# Rotary_Encoder.net
KiCad netlist of a schematic drawn in Altium Designer
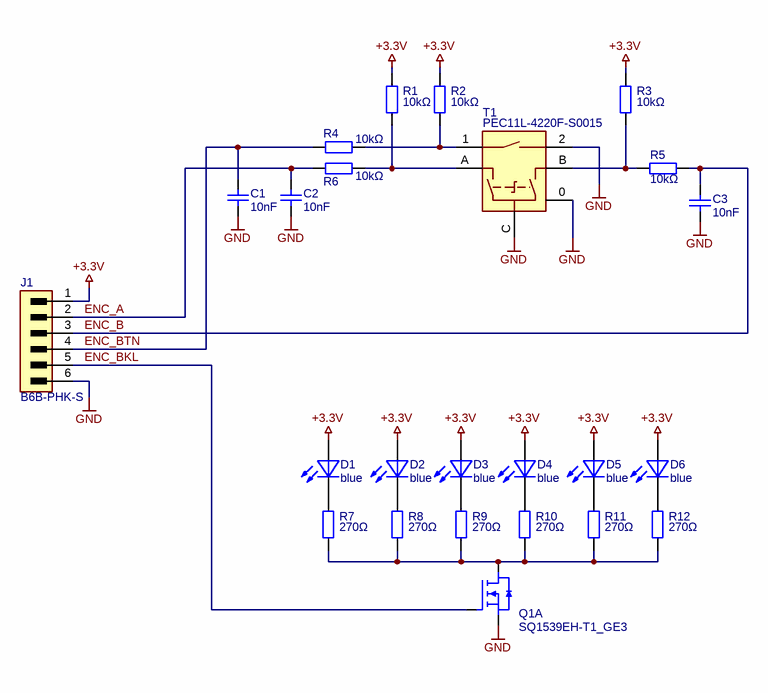
[diagram p0: Rotary Encoder.SchDoc]

(export (version "E")
  (design (tool "Eeschema 10.0.6"))
  (components
    (comp (ref "C1")
      (value "10nF")
      (footprint "SMD0603CAP")
      (description "Ceramic Capacitor")
      (libsource (lib "Audio-Streamer") (part "Capacitor Ceramic"))
    )
    (comp (ref "C2")
      (value "10nF")
      (footprint "SMD0603CAP")
      (description "Ceramic Capacitor")
      (libsource (lib "Audio-Streamer") (part "Capacitor Ceramic"))
    )
    (comp (ref "C3")
      (value "10nF")
      (footprint "SMD0603CAP")
      (description "Ceramic Capacitor")
      (libsource (lib "Audio-Streamer") (part "Capacitor Ceramic"))
    )
    (comp (ref "D1")
      (value "blue")
      (footprint "LED")
      (description "LED red")
      (fields (field (name "MANUFACTURER PART NO.") "LB M673-M1N2-35-Z"))
      (libsource (lib "Audio-Streamer") (part "LED red"))
    )
    (comp (ref "D2")
      (value "blue")
      (footprint "LED")
      (description "LED red")
      (fields (field (name "MANUFACTURER PART NO.") "LB M673-M1N2-35-Z"))
      (libsource (lib "Audio-Streamer") (part "LED red"))
    )
    (comp (ref "D3")
      (value "blue")
      (footprint "LED")
      (description "LED red")
      (fields (field (name "MANUFACTURER PART NO.") "LB M673-M1N2-35-Z"))
      (libsource (lib "Audio-Streamer") (part "LED red"))
    )
    (comp (ref "D4")
      (value "blue")
      (footprint "LED")
      (description "LED red")
      (fields (field (name "MANUFACTURER PART NO.") "LB M673-M1N2-35-Z"))
      (libsource (lib "Audio-Streamer") (part "LED red"))
    )
    (comp (ref "D5")
      (value "blue")
      (footprint "LED")
      (description "LED red")
      (fields (field (name "MANUFACTURER PART NO.") "LB M673-M1N2-35-Z"))
      (libsource (lib "Audio-Streamer") (part "LED red"))
    )
    (comp (ref "D6")
      (value "blue")
      (footprint "LED")
      (description "LED red")
      (fields (field (name "MANUFACTURER PART NO.") "LB M673-M1N2-35-Z"))
      (libsource (lib "Audio-Streamer") (part "LED red"))
    )
    (comp (ref "J1")
      (value "B6B-PHK-S")
      (footprint "B6B-PH-K-S")
      (description "Connector 6x1P")
      (libsource (lib "Audio-Streamer") (part "Connector 6x1P"))
    )
    (comp (ref "Q1")
      (value "SQ1539EH-T1_GE3")
      (footprint "SOT-363-6")
      (description "Transistor Dual, NMOS & PMOS")
      (libsource (lib "Audio-Streamer") (part "Transistor N/PMOS Dual"))
    )
    (comp (ref "R1")
      (value "10kΩ")
      (footprint "SMD0603RES")
      (description "Resistor")
      (libsource (lib "") (part "Resistor_1"))
    )
    (comp (ref "R2")
      (value "10kΩ")
      (footprint "SMD0603RES")
      (description "Resistor")
      (libsource (lib "") (part "Resistor_1"))
    )
    (comp (ref "R3")
      (value "10kΩ")
      (footprint "SMD0603RES")
      (description "Resistor")
      (libsource (lib "") (part "Resistor_2"))
    )
    (comp (ref "R4")
      (value "10kΩ")
      (footprint "SMD0603RES")
      (description "Resistor")
      (libsource (lib "Audio-Streamer") (part "Resistor"))
    )
    (comp (ref "R5")
      (value "10kΩ")
      (footprint "SMD0603RES")
      (description "Resistor")
      (libsource (lib "") (part "Resistor_1"))
    )
    (comp (ref "R6")
      (value "10kΩ")
      (footprint "SMD0603RES")
      (description "Resistor")
      (libsource (lib "Audio-Streamer") (part "Resistor"))
    )
    (comp (ref "R7")
      (value "270Ω")
      (footprint "SMD0603RES")
      (description "Resistor")
      (libsource (lib "Audio-Streamer") (part "Resistor"))
    )
    (comp (ref "R8")
      (value "270Ω")
      (footprint "SMD0603RES")
      (description "Resistor")
      (libsource (lib "Audio-Streamer") (part "Resistor"))
    )
    (comp (ref "R9")
      (value "270Ω")
      (footprint "SMD0603RES")
      (description "Resistor")
      (libsource (lib "Audio-Streamer") (part "Resistor"))
    )
    (comp (ref "R10")
      (value "270Ω")
      (footprint "SMD0603RES")
      (description "Resistor")
      (libsource (lib "Audio-Streamer") (part "Resistor"))
    )
    (comp (ref "R11")
      (value "270Ω")
      (footprint "SMD0603RES")
      (description "Resistor")
      (libsource (lib "Audio-Streamer") (part "Resistor"))
    )
    (comp (ref "R12")
      (value "270Ω")
      (footprint "SMD0603RES")
      (description "Resistor")
      (libsource (lib "Audio-Streamer") (part "Resistor"))
    )
    (comp (ref "T1")
      (value "PEC11L-4220F-S0015")
      (footprint "PEC11L-4220F-S0015")
      (description "Rotary Encoder with button")
      (libsource (lib "Audio-Streamer") (part "Rotary Encoder"))
    )
  )
  (nets
    (net (code "1") (name "+3.3V") (class "Default")
      (node (ref "D1") (pin "A") (pinfunction "A_A") (pintype "passive"))
      (node (ref "D2") (pin "A") (pinfunction "A_A") (pintype "passive"))
      (node (ref "D3") (pin "A") (pinfunction "A_A") (pintype "passive"))
      (node (ref "D4") (pin "A") (pinfunction "A_A") (pintype "passive"))
      (node (ref "D5") (pin "A") (pinfunction "A_A") (pintype "passive"))
      (node (ref "D6") (pin "A") (pinfunction "A_A") (pintype "passive"))
      (node (ref "J1") (pin "1") (pinfunction "1_1") (pintype "passive"))
      (node (ref "R1") (pin "1") (pinfunction "1_1") (pintype "passive"))
      (node (ref "R2") (pin "1") (pinfunction "1_1") (pintype "passive"))
      (node (ref "R3") (pin "1") (pinfunction "1_1") (pintype "passive"))
    )
    (net (code "2") (name "/ENC_A") (class "Default")
      (node (ref "C2") (pin "1") (pinfunction "1_1") (pintype "passive"))
      (node (ref "J1") (pin "2") (pinfunction "2_2") (pintype "passive"))
      (node (ref "R6") (pin "1") (pinfunction "1_1") (pintype "passive"))
    )
    (net (code "3") (name "/ENC_B") (class "Default")
      (node (ref "C3") (pin "1") (pinfunction "1_1") (pintype "passive"))
      (node (ref "J1") (pin "3") (pinfunction "3_3") (pintype "passive"))
      (node (ref "R5") (pin "1") (pinfunction "1_1") (pintype "passive"))
    )
    (net (code "4") (name "/ENC_BKL") (class "Default")
      (node (ref "J1") (pin "5") (pinfunction "5_5") (pintype "passive"))
      (node (ref "Q1") (pin "2") (pinfunction "G_2") (pintype "passive"))
    )
    (net (code "5") (name "/ENC_BTN") (class "Default")
      (node (ref "C1") (pin "1") (pinfunction "1_1") (pintype "passive"))
      (node (ref "J1") (pin "4") (pinfunction "4_4") (pintype "passive"))
      (node (ref "R4") (pin "1") (pinfunction "1_1") (pintype "passive"))
    )
    (net (code "6") (name "GND") (class "Default")
      (node (ref "C1") (pin "2") (pinfunction "q_2") (pintype "passive"))
      (node (ref "C2") (pin "2") (pinfunction "q_2") (pintype "passive"))
      (node (ref "C3") (pin "2") (pinfunction "q_2") (pintype "passive"))
      (node (ref "J1") (pin "6") (pinfunction "6_6") (pintype "passive"))
      (node (ref "Q1") (pin "1") (pinfunction "S_1") (pintype "passive"))
      (node (ref "T1") (pin "0") (pinfunction "0_0") (pintype "passive"))
      (node (ref "T1") (pin "2") (pinfunction "2_2") (pintype "passive"))
      (node (ref "T1") (pin "C") (pinfunction "C_C") (pintype "passive"))
    )
    (net (code "7") (name "Net-(D1-PadC)") (class "Default")
      (node (ref "D1") (pin "C") (pinfunction "C_C") (pintype "passive"))
      (node (ref "R7") (pin "2") (pinfunction "2_2") (pintype "passive"))
    )
    (net (code "8") (name "Net-(D2-PadC)") (class "Default")
      (node (ref "D2") (pin "C") (pinfunction "C_C") (pintype "passive"))
      (node (ref "R8") (pin "2") (pinfunction "2_2") (pintype "passive"))
    )
    (net (code "9") (name "Net-(D3-PadC)") (class "Default")
      (node (ref "D3") (pin "C") (pinfunction "C_C") (pintype "passive"))
      (node (ref "R9") (pin "2") (pinfunction "2_2") (pintype "passive"))
    )
    (net (code "10") (name "Net-(D4-PadC)") (class "Default")
      (node (ref "D4") (pin "C") (pinfunction "C_C") (pintype "passive"))
      (node (ref "R10") (pin "2") (pinfunction "2_2") (pintype "passive"))
    )
    (net (code "11") (name "Net-(D5-PadC)") (class "Default")
      (node (ref "D5") (pin "C") (pinfunction "C_C") (pintype "passive"))
      (node (ref "R11") (pin "2") (pinfunction "2_2") (pintype "passive"))
    )
    (net (code "12") (name "Net-(D6-PadC)") (class "Default")
      (node (ref "D6") (pin "C") (pinfunction "C_C") (pintype "passive"))
      (node (ref "R12") (pin "2") (pinfunction "2_2") (pintype "passive"))
    )
    (net (code "13") (name "Net-(Q1A-D)") (class "Default")
      (node (ref "Q1") (pin "6") (pinfunction "D_6") (pintype "passive"))
      (node (ref "R10") (pin "1") (pinfunction "1_1") (pintype "passive"))
      (node (ref "R11") (pin "1") (pinfunction "1_1") (pintype "passive"))
      (node (ref "R12") (pin "1") (pinfunction "1_1") (pintype "passive"))
      (node (ref "R7") (pin "1") (pinfunction "1_1") (pintype "passive"))
      (node (ref "R8") (pin "1") (pinfunction "1_1") (pintype "passive"))
      (node (ref "R9") (pin "1") (pinfunction "1_1") (pintype "passive"))
    )
    (net (code "14") (name "Net-(R1-Pad2)") (class "Default")
      (node (ref "R1") (pin "2") (pinfunction "2_2") (pintype "passive"))
      (node (ref "R6") (pin "2") (pinfunction "2_2") (pintype "passive"))
      (node (ref "T1") (pin "A") (pinfunction "A_A") (pintype "passive"))
    )
    (net (code "15") (name "Net-(R2-Pad2)") (class "Default")
      (node (ref "R2") (pin "2") (pinfunction "2_2") (pintype "passive"))
      (node (ref "R4") (pin "2") (pinfunction "2_2") (pintype "passive"))
      (node (ref "T1") (pin "1") (pinfunction "1_1") (pintype "passive"))
    )
    (net (code "16") (name "Net-(R3-Pad2)") (class "Default")
      (node (ref "R3") (pin "2") (pinfunction "2_2") (pintype "passive"))
      (node (ref "R5") (pin "2") (pinfunction "2_2") (pintype "passive"))
      (node (ref "T1") (pin "B") (pinfunction "B_B") (pintype "passive"))
    )
  )
)
